# BOARD1_module.net
KiCad netlist of a schematic drawn in Altium Designer
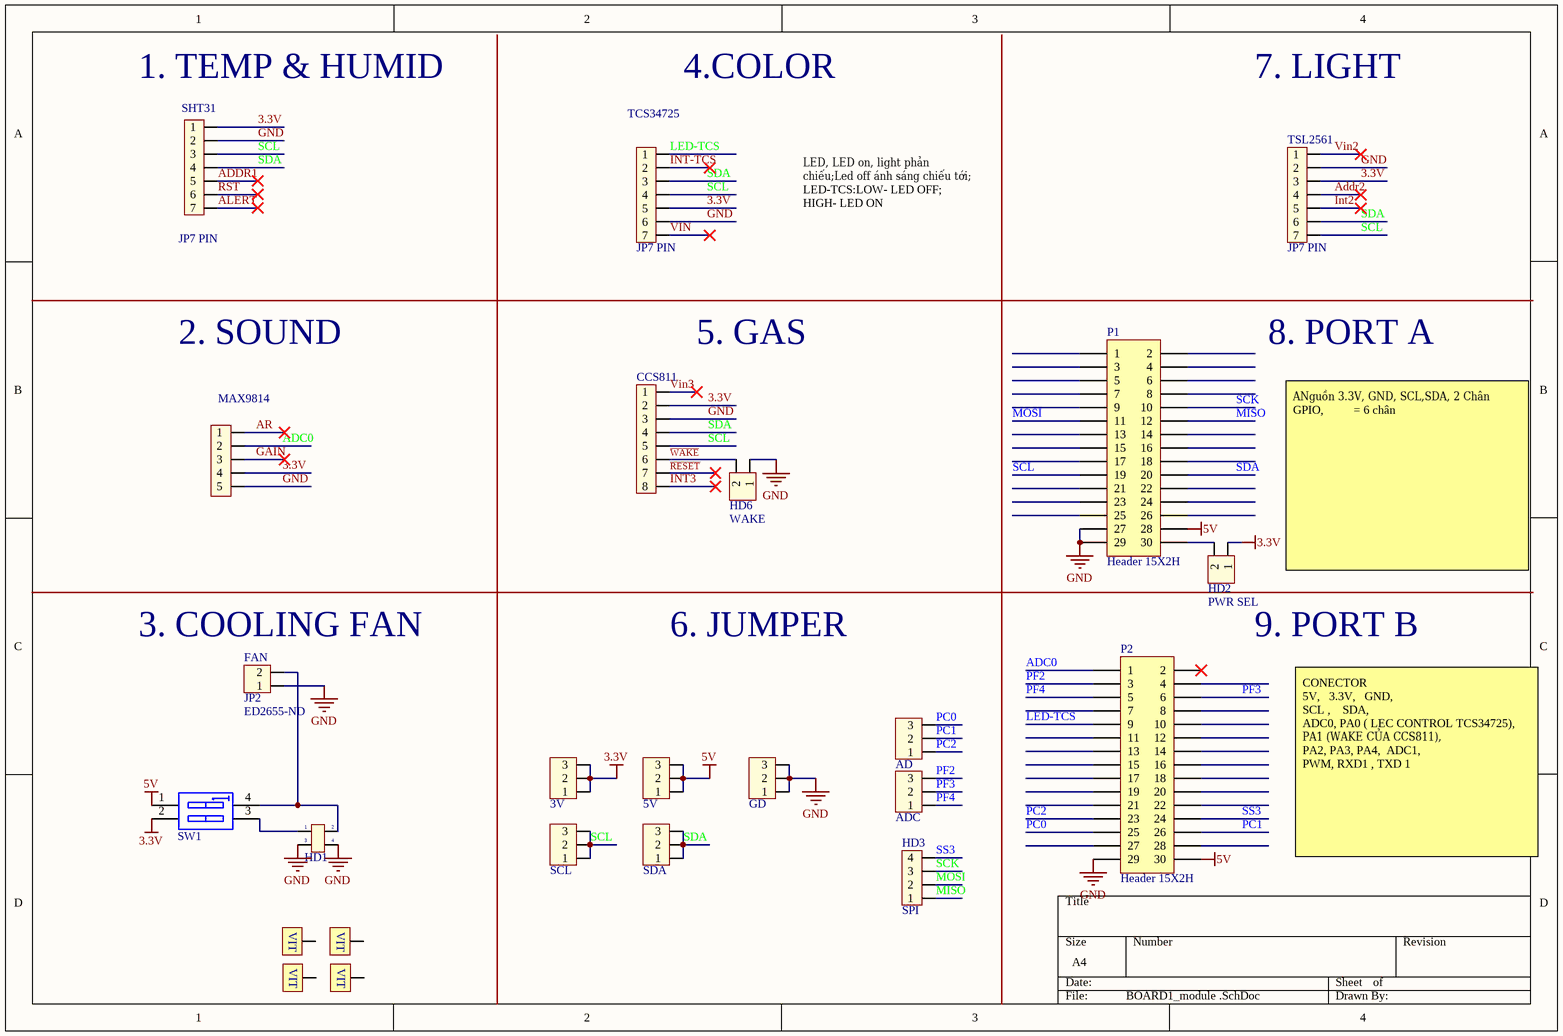
[diagram p0: BOARD1_module .SchDoc]

(export (version "E")
  (design (tool "Eeschema 10.0.6"))
  (components
    (comp (ref "3V") (value "Header 3") (footprint "Header_3") (libsource (lib "lpson") (part "Header3")))
    (comp (ref "5V") (value "Header 3") (footprint "Header_3") (libsource (lib "lpson") (part "Header3")))
    (comp (ref "AD") (value "Header 3") (footprint "Header_3") (libsource (lib "lpson") (part "Header3")))
    (comp (ref "ADC") (value "Header 3") (footprint "Header_3") (libsource (lib "lpson") (part "Header3")))
    (comp (ref "CCS811")
      (value "JP8 PIN")
      (footprint "CCS811")
      (libsource (lib "quangnguyen_lib_altium") (part "JP8"))
    )
    (comp (ref "FAN")
      (value "JP2")
      (footprint "CON2")
      (description "Terminal 2pin 5mm")
      (fields
        (field (name "MANUFACTURER") "On Shore Technology Inc.")
        (field (name "MANUFACTURER PART NUMBER") "OSTTH020160")
        (field (name "SUPPLIER PART NUMBER 1") "ED2655-ND")
      )
      (libsource (lib "lpson") (part "Terminal 2"))
    )
    (comp (ref "GD") (value "Header 3") (footprint "Header_3") (libsource (lib "lpson") (part "Header3")))
    (comp (ref "HD1") (value "Jumper 2x2") (footprint "HDR2X2") (libsource (lib "lpson") (part "JP2x2")))
    (comp (ref "HD2")
      (value "PWR SEL")
      (footprint "Header_2")
      (description "Header 2")
      (libsource (lib "lpson") (part "Header2"))
    )
    (comp (ref "HD3")
      (value "SPI")
      (footprint "Header_4")
      (description "Header 4")
      (libsource (lib "lpson") (part "Header4"))
    )
    (comp (ref "HD6")
      (value "WAKE")
      (footprint "Header_2")
      (description "Header 2")
      (libsource (lib "lpson") (part "Header2"))
    )
    (comp (ref "MAX9814")
      (value "JP5")
      (footprint "MAX9814")
      (libsource (lib "quangnguyen_lib_altium") (part "JP5"))
    )
    (comp (ref "P1")
      (value "Header 15X2H")
      (footprint "HED15X2H")
      (description "Header, 15-Pin, Dual row, Right Angle")
      (fields (field (name "PUBLISHER") "Altium Limited"))
      (libsource (lib "My Library") (part "Header 15X2H"))
    )
    (comp (ref "P2")
      (value "Header 15X2H")
      (footprint "HED15X2H")
      (description "Header, 15-Pin, Dual row, Right Angle")
      (fields (field (name "PUBLISHER") "Altium Limited"))
      (libsource (lib "My Library") (part "Header 15X2H"))
    )
    (comp (ref "SCL") (value "Header 3") (footprint "Header_3") (libsource (lib "lpson") (part "Header3")))
    (comp (ref "SDA") (value "Header 3") (footprint "Header_3") (libsource (lib "lpson") (part "Header3")))
    (comp (ref "SHT31")
      (value "JP7 PIN")
      (footprint "SHT31")
      (libsource (lib "quangnguyen_lib_altium") (part "JP7"))
    )
    (comp (ref "SW1")
      (value "SW - DIP2")
      (footprint "DIP_Switch2")
      (description "DIP Switch, 2 Position, SPST")
      (libsource (lib "lpson") (part "SWDIP-2"))
    )
    (comp (ref "TCS34725")
      (value "JP7 PIN")
      (footprint "TCS34725")
      (libsource (lib "quangnguyen_lib_altium") (part "JP7"))
    )
    (comp (ref "TSL2561")
      (value "JP7 PIN")
      (footprint "TSL2561")
      (libsource (lib "quangnguyen_lib_altium") (part "JP7"))
    )
    (comp (ref "VIT2")
      (value "1")
      (footprint "Screw 3 small")
      (description "Oc Vit")
      (libsource (lib "quangnguyen_lib_altium") (part "VIT"))
    )
    (comp (ref "VIT3")
      (value "1")
      (footprint "Screw 3 small")
      (description "Oc Vit")
      (libsource (lib "quangnguyen_lib_altium") (part "VIT"))
    )
    (comp (ref "VIT5")
      (value "1")
      (footprint "Screw 3 small")
      (description "Oc Vit")
      (libsource (lib "quangnguyen_lib_altium") (part "VIT"))
    )
    (comp (ref "VIT6")
      (value "1")
      (footprint "Screw 3 small")
      (description "Oc Vit")
      (libsource (lib "quangnguyen_lib_altium") (part "VIT"))
    )
  )
  (nets
    (net (code "1") (name "/ADC0") (class "Default")
      (node (ref "MAX9814") (pin "2") (pinfunction "2_2") (pintype "passive"))
      (node (ref "P2") (pin "1") (pinfunction "1_1") (pintype "passive"))
    )
    (net (code "2") (name "/ADDR1") (class "Default")
      (node (ref "SHT31") (pin "5") (pinfunction "5_5") (pintype "passive+no_connect"))
    )
    (net (code "3") (name "/ALERT") (class "Default")
      (node (ref "SHT31") (pin "7") (pinfunction "7_7") (pintype "passive+no_connect"))
    )
    (net (code "4") (name "/AR") (class "Default")
      (node (ref "MAX9814") (pin "1") (pinfunction "1_1") (pintype "passive+no_connect"))
    )
    (net (code "5") (name "/Addr2") (class "Default")
      (node (ref "TSL2561") (pin "4") (pinfunction "4_4") (pintype "passive+no_connect"))
    )
    (net (code "6") (name "/GAIN") (class "Default")
      (node (ref "MAX9814") (pin "3") (pinfunction "3_3") (pintype "passive+no_connect"))
    )
    (net (code "7") (name "/INT-TCS") (class "Default")
      (node (ref "TCS34725") (pin "2") (pinfunction "2_2") (pintype "passive+no_connect"))
    )
    (net (code "8") (name "/INT3") (class "Default")
      (node (ref "CCS811") (pin "8") (pinfunction "8_8") (pintype "passive+no_connect"))
    )
    (net (code "9") (name "/Int2") (class "Default")
      (node (ref "TSL2561") (pin "5") (pinfunction "5_5") (pintype "passive+no_connect"))
    )
    (net (code "10") (name "/LED-TCS") (class "Default")
      (node (ref "P2") (pin "9") (pinfunction "9_9") (pintype "passive"))
      (node (ref "TCS34725") (pin "1") (pinfunction "1_1") (pintype "passive"))
    )
    (net (code "11") (name "/MISO") (class "Default")
      (node (ref "HD3") (pin "1") (pinfunction "1_1") (pintype "passive"))
      (node (ref "P1") (pin "12") (pinfunction "12_12") (pintype "passive"))
    )
    (net (code "12") (name "/MOSI") (class "Default")
      (node (ref "HD3") (pin "2") (pinfunction "2_2") (pintype "passive"))
      (node (ref "P1") (pin "11") (pinfunction "11_11") (pintype "passive"))
    )
    (net (code "13") (name "/PC0") (class "Default")
      (node (ref "AD") (pin "3") (pinfunction "3_3") (pintype "passive"))
      (node (ref "P2") (pin "25") (pinfunction "25_25") (pintype "passive"))
    )
    (net (code "14") (name "/PC1") (class "Default")
      (node (ref "AD") (pin "2") (pinfunction "2_2") (pintype "passive"))
      (node (ref "P2") (pin "26") (pinfunction "26_26") (pintype "passive"))
    )
    (net (code "15") (name "/PC2") (class "Default")
      (node (ref "AD") (pin "1") (pinfunction "1_1") (pintype "passive"))
      (node (ref "P2") (pin "23") (pinfunction "23_23") (pintype "passive"))
    )
    (net (code "16") (name "/PF2") (class "Default")
      (node (ref "ADC") (pin "3") (pinfunction "3_3") (pintype "passive"))
      (node (ref "P2") (pin "3") (pinfunction "3_3") (pintype "passive"))
    )
    (net (code "17") (name "/PF3") (class "Default")
      (node (ref "ADC") (pin "2") (pinfunction "2_2") (pintype "passive"))
      (node (ref "P2") (pin "6") (pinfunction "6_6") (pintype "passive"))
    )
    (net (code "18") (name "/PF4") (class "Default")
      (node (ref "ADC") (pin "1") (pinfunction "1_1") (pintype "passive"))
      (node (ref "P2") (pin "5") (pinfunction "5_5") (pintype "passive"))
    )
    (net (code "19") (name "/RST") (class "Default")
      (node (ref "SHT31") (pin "6") (pinfunction "6_6") (pintype "passive+no_connect"))
    )
    (net (code "20") (name "/SCK") (class "Default")
      (node (ref "HD3") (pin "3") (pinfunction "3_3") (pintype "passive"))
      (node (ref "P1") (pin "10") (pinfunction "10_10") (pintype "passive"))
    )
    (net (code "21") (name "/SCL") (class "Default")
      (node (ref "CCS811") (pin "5") (pinfunction "5_5") (pintype "passive"))
      (node (ref "P1") (pin "19") (pinfunction "19_19") (pintype "passive"))
      (node (ref "SCL") (pin "1") (pinfunction "1_1") (pintype "passive"))
      (node (ref "SCL") (pin "2") (pinfunction "2_2") (pintype "passive"))
      (node (ref "SCL") (pin "3") (pinfunction "3_3") (pintype "passive"))
      (node (ref "SHT31") (pin "3") (pinfunction "3_3") (pintype "passive"))
      (node (ref "TCS34725") (pin "4") (pinfunction "4_4") (pintype "passive"))
      (node (ref "TSL2561") (pin "7") (pinfunction "7_7") (pintype "passive"))
    )
    (net (code "22") (name "/SDA") (class "Default")
      (node (ref "CCS811") (pin "4") (pinfunction "4_4") (pintype "passive"))
      (node (ref "P1") (pin "20") (pinfunction "20_20") (pintype "passive"))
      (node (ref "SDA") (pin "1") (pinfunction "1_1") (pintype "passive"))
      (node (ref "SDA") (pin "2") (pinfunction "2_2") (pintype "passive"))
      (node (ref "SDA") (pin "3") (pinfunction "3_3") (pintype "passive"))
      (node (ref "SHT31") (pin "4") (pinfunction "4_4") (pintype "passive"))
      (node (ref "TCS34725") (pin "3") (pinfunction "3_3") (pintype "passive"))
      (node (ref "TSL2561") (pin "6") (pinfunction "6_6") (pintype "passive"))
    )
    (net (code "23") (name "/SS3") (class "Default")
      (node (ref "HD3") (pin "4") (pinfunction "4_4") (pintype "passive"))
      (node (ref "P2") (pin "24") (pinfunction "24_24") (pintype "passive"))
    )
    (net (code "24") (name "/VIN") (class "Default")
      (node (ref "TCS34725") (pin "7") (pinfunction "7_7") (pintype "passive+no_connect"))
    )
    (net (code "25") (name "/Vin2") (class "Default")
      (node (ref "TSL2561") (pin "1") (pinfunction "1_1") (pintype "passive+no_connect"))
    )
    (net (code "26") (name "/Vin3") (class "Default")
      (node (ref "CCS811") (pin "1") (pinfunction "1_1") (pintype "passive+no_connect"))
    )
    (net (code "27") (name "/~{RESET}") (class "Default")
      (node (ref "CCS811") (pin "7") (pinfunction "7_7") (pintype "passive+no_connect"))
    )
    (net (code "28") (name "/~{WAKE}") (class "Default")
      (node (ref "CCS811") (pin "6") (pinfunction "6_6") (pintype "passive"))
      (node (ref "HD6") (pin "2") (pinfunction "2_2") (pintype "passive"))
    )
    (net (code "29") (name "3.3V") (class "Default")
      (node (ref "3V") (pin "1") (pinfunction "1_1") (pintype "passive"))
      (node (ref "3V") (pin "2") (pinfunction "2_2") (pintype "passive"))
      (node (ref "3V") (pin "3") (pinfunction "3_3") (pintype "passive"))
      (node (ref "CCS811") (pin "2") (pinfunction "2_2") (pintype "passive"))
      (node (ref "HD2") (pin "1") (pinfunction "1_1") (pintype "passive"))
      (node (ref "MAX9814") (pin "4") (pinfunction "4_4") (pintype "passive"))
      (node (ref "SHT31") (pin "1") (pinfunction "1_1") (pintype "passive"))
      (node (ref "SW1") (pin "2") (pinfunction "A2_2") (pintype "passive"))
      (node (ref "TCS34725") (pin "5") (pinfunction "5_5") (pintype "passive"))
      (node (ref "TSL2561") (pin "3") (pinfunction "3_3") (pintype "passive"))
    )
    (net (code "30") (name "5V") (class "Default")
      (node (ref "5V") (pin "1") (pinfunction "1_1") (pintype "passive"))
      (node (ref "5V") (pin "2") (pinfunction "2_2") (pintype "passive"))
      (node (ref "5V") (pin "3") (pinfunction "3_3") (pintype "passive"))
      (node (ref "P1") (pin "28") (pinfunction "28_28") (pintype "passive"))
      (node (ref "P2") (pin "30") (pinfunction "30_30") (pintype "passive"))
      (node (ref "SW1") (pin "1") (pinfunction "A1_1") (pintype "passive"))
    )
    (net (code "31") (name "GND") (class "Default")
      (node (ref "CCS811") (pin "3") (pinfunction "3_3") (pintype "passive"))
      (node (ref "FAN") (pin "1") (pinfunction "1_1") (pintype "passive"))
      (node (ref "GD") (pin "1") (pinfunction "1_1") (pintype "passive"))
      (node (ref "GD") (pin "2") (pinfunction "2_2") (pintype "passive"))
      (node (ref "GD") (pin "3") (pinfunction "3_3") (pintype "passive"))
      (node (ref "HD1") (pin "3") (pinfunction "3_3") (pintype "passive"))
      (node (ref "HD1") (pin "4") (pinfunction "4_4") (pintype "passive"))
      (node (ref "HD6") (pin "1") (pinfunction "1_1") (pintype "passive"))
      (node (ref "MAX9814") (pin "5") (pinfunction "5_5") (pintype "passive"))
      (node (ref "P1") (pin "27") (pinfunction "27_27") (pintype "passive"))
      (node (ref "P1") (pin "29") (pinfunction "29_29") (pintype "passive"))
      (node (ref "P2") (pin "29") (pinfunction "29_29") (pintype "passive"))
      (node (ref "SHT31") (pin "2") (pinfunction "2_2") (pintype "passive"))
      (node (ref "TCS34725") (pin "6") (pinfunction "6_6") (pintype "passive"))
      (node (ref "TSL2561") (pin "2") (pinfunction "2_2") (pintype "passive"))
    )
    (net (code "32") (name "Net-(HD2-Pad2)") (class "Default")
      (node (ref "HD2") (pin "2") (pinfunction "2_2") (pintype "passive"))
      (node (ref "P1") (pin "30") (pinfunction "30_30") (pintype "passive"))
    )
    (net (code "33") (name "Net-(SW1-A3)") (class "Default")
      (node (ref "HD1") (pin "1") (pinfunction "1_1") (pintype "passive"))
      (node (ref "SW1") (pin "3") (pinfunction "A3_3") (pintype "passive"))
    )
    (net (code "34") (name "Net-(SW1-A4)") (class "Default")
      (node (ref "FAN") (pin "2") (pinfunction "2_2") (pintype "passive"))
      (node (ref "HD1") (pin "2") (pinfunction "2_2") (pintype "passive"))
      (node (ref "SW1") (pin "4") (pinfunction "A4_4") (pintype "passive"))
    )
    (net (code "35") (name "unconnected-(P1-Pad1)") (class "Default")
      (node (ref "P1") (pin "1") (pinfunction "1_1") (pintype "passive"))
    )
    (net (code "36") (name "unconnected-(P1-Pad2)") (class "Default")
      (node (ref "P1") (pin "2") (pinfunction "2_2") (pintype "passive"))
    )
    (net (code "37") (name "unconnected-(P1-Pad3)") (class "Default")
      (node (ref "P1") (pin "3") (pinfunction "3_3") (pintype "passive"))
    )
    (net (code "38") (name "unconnected-(P1-Pad4)") (class "Default")
      (node (ref "P1") (pin "4") (pinfunction "4_4") (pintype "passive"))
    )
    (net (code "39") (name "unconnected-(P1-Pad5)") (class "Default")
      (node (ref "P1") (pin "5") (pinfunction "5_5") (pintype "passive"))
    )
    (net (code "40") (name "unconnected-(P1-Pad6)") (class "Default")
      (node (ref "P1") (pin "6") (pinfunction "6_6") (pintype "passive"))
    )
    (net (code "41") (name "unconnected-(P1-Pad7)") (class "Default")
      (node (ref "P1") (pin "7") (pinfunction "7_7") (pintype "passive"))
    )
    (net (code "42") (name "unconnected-(P1-Pad8)") (class "Default")
      (node (ref "P1") (pin "8") (pinfunction "8_8") (pintype "passive"))
    )
    (net (code "43") (name "unconnected-(P1-Pad9)") (class "Default")
      (node (ref "P1") (pin "9") (pinfunction "9_9") (pintype "passive"))
    )
    (net (code "44") (name "unconnected-(P1-Pad13)") (class "Default")
      (node (ref "P1") (pin "13") (pinfunction "13_13") (pintype "passive"))
    )
    (net (code "45") (name "unconnected-(P1-Pad14)") (class "Default")
      (node (ref "P1") (pin "14") (pinfunction "14_14") (pintype "passive"))
    )
    (net (code "46") (name "unconnected-(P1-Pad15)") (class "Default")
      (node (ref "P1") (pin "15") (pinfunction "15_15") (pintype "passive"))
    )
    (net (code "47") (name "unconnected-(P1-Pad16)") (class "Default")
      (node (ref "P1") (pin "16") (pinfunction "16_16") (pintype "passive"))
    )
    (net (code "48") (name "unconnected-(P1-Pad17)") (class "Default")
      (node (ref "P1") (pin "17") (pinfunction "17_17") (pintype "passive"))
    )
    (net (code "49") (name "unconnected-(P1-Pad18)") (class "Default")
      (node (ref "P1") (pin "18") (pinfunction "18_18") (pintype "passive"))
    )
    (net (code "50") (name "unconnected-(P1-Pad21)") (class "Default")
      (node (ref "P1") (pin "21") (pinfunction "21_21") (pintype "passive"))
    )
    (net (code "51") (name "unconnected-(P1-Pad22)") (class "Default")
      (node (ref "P1") (pin "22") (pinfunction "22_22") (pintype "passive"))
    )
    (net (code "52") (name "unconnected-(P1-Pad23)") (class "Default")
      (node (ref "P1") (pin "23") (pinfunction "23_23") (pintype "passive"))
    )
    (net (code "53") (name "unconnected-(P1-Pad24)") (class "Default")
      (node (ref "P1") (pin "24") (pinfunction "24_24") (pintype "passive"))
    )
    (net (code "54") (name "unconnected-(P1-Pad25)") (class "Default")
      (node (ref "P1") (pin "25") (pinfunction "25_25") (pintype "passive"))
    )
    (net (code "55") (name "unconnected-(P1-Pad26)") (class "Default")
      (node (ref "P1") (pin "26") (pinfunction "26_26") (pintype "passive"))
    )
    (net (code "56") (name "unconnected-(P2-Pad2)") (class "Default")
      (node (ref "P2") (pin "2") (pinfunction "2_2") (pintype "passive+no_connect"))
    )
    (net (code "57") (name "unconnected-(P2-Pad4)") (class "Default")
      (node (ref "P2") (pin "4") (pinfunction "4_4") (pintype "passive"))
    )
    (net (code "58") (name "unconnected-(P2-Pad7)") (class "Default")
      (node (ref "P2") (pin "7") (pinfunction "7_7") (pintype "passive"))
    )
    (net (code "59") (name "unconnected-(P2-Pad8)") (class "Default")
      (node (ref "P2") (pin "8") (pinfunction "8_8") (pintype "passive"))
    )
    (net (code "60") (name "unconnected-(P2-Pad10)") (class "Default")
      (node (ref "P2") (pin "10") (pinfunction "10_10") (pintype "passive"))
    )
    (net (code "61") (name "unconnected-(P2-Pad11)") (class "Default")
      (node (ref "P2") (pin "11") (pinfunction "11_11") (pintype "passive"))
    )
    (net (code "62") (name "unconnected-(P2-Pad12)") (class "Default")
      (node (ref "P2") (pin "12") (pinfunction "12_12") (pintype "passive"))
    )
    (net (code "63") (name "unconnected-(P2-Pad13)") (class "Default")
      (node (ref "P2") (pin "13") (pinfunction "13_13") (pintype "passive"))
    )
    (net (code "64") (name "unconnected-(P2-Pad14)") (class "Default")
      (node (ref "P2") (pin "14") (pinfunction "14_14") (pintype "passive"))
    )
    (net (code "65") (name "unconnected-(P2-Pad15)") (class "Default")
      (node (ref "P2") (pin "15") (pinfunction "15_15") (pintype "passive"))
    )
    (net (code "66") (name "unconnected-(P2-Pad16)") (class "Default")
      (node (ref "P2") (pin "16") (pinfunction "16_16") (pintype "passive"))
    )
    (net (code "67") (name "unconnected-(P2-Pad17)") (class "Default")
      (node (ref "P2") (pin "17") (pinfunction "17_17") (pintype "passive"))
    )
    (net (code "68") (name "unconnected-(P2-Pad18)") (class "Default")
      (node (ref "P2") (pin "18") (pinfunction "18_18") (pintype "passive"))
    )
    (net (code "69") (name "unconnected-(P2-Pad19)") (class "Default")
      (node (ref "P2") (pin "19") (pinfunction "19_19") (pintype "passive"))
    )
    (net (code "70") (name "unconnected-(P2-Pad20)") (class "Default")
      (node (ref "P2") (pin "20") (pinfunction "20_20") (pintype "passive"))
    )
    (net (code "71") (name "unconnected-(P2-Pad21)") (class "Default")
      (node (ref "P2") (pin "21") (pinfunction "21_21") (pintype "passive"))
    )
    (net (code "72") (name "unconnected-(P2-Pad22)") (class "Default")
      (node (ref "P2") (pin "22") (pinfunction "22_22") (pintype "passive"))
    )
    (net (code "73") (name "unconnected-(P2-Pad27)") (class "Default")
      (node (ref "P2") (pin "27") (pinfunction "27_27") (pintype "passive"))
    )
    (net (code "74") (name "unconnected-(P2-Pad28)") (class "Default")
      (node (ref "P2") (pin "28") (pinfunction "28_28") (pintype "passive"))
    )
    (net (code "75") (name "unconnected-(VIT2-1-PadVIT1)") (class "Default")
      (node (ref "VIT2") (pin "VIT1") (pinfunction "1_VIT1") (pintype "passive"))
    )
    (net (code "76") (name "unconnected-(VIT3-1-PadVIT1)") (class "Default")
      (node (ref "VIT3") (pin "VIT1") (pinfunction "1_VIT1") (pintype "passive"))
    )
    (net (code "77") (name "unconnected-(VIT5-1-PadVIT1)") (class "Default")
      (node (ref "VIT5") (pin "VIT1") (pinfunction "1_VIT1") (pintype "passive"))
    )
    (net (code "78") (name "unconnected-(VIT6-1-PadVIT1)") (class "Default")
      (node (ref "VIT6") (pin "VIT1") (pinfunction "1_VIT1") (pintype "passive"))
    )
  )
)
